# arduino-pro-micro.net
KiCad netlist of a schematic drawn in EAGLE
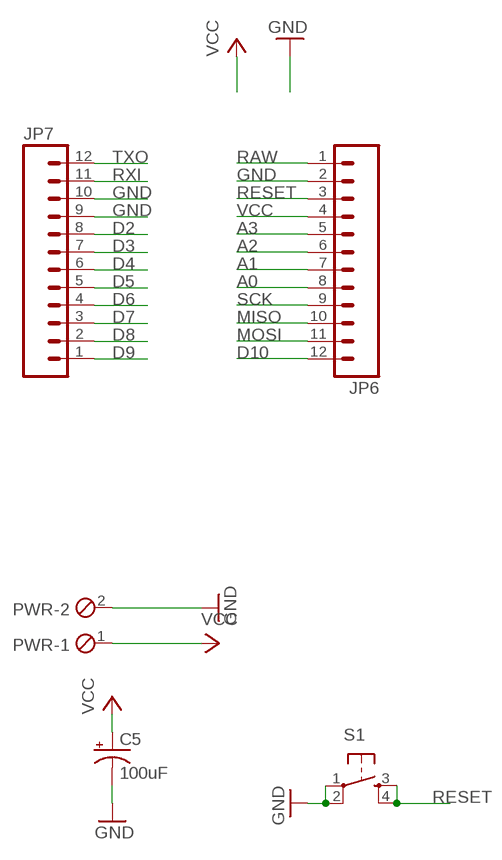
[diagram p0: schematic, sheet 1]

(export (version "E")
  (design (tool "Eeschema 10.0.6"))
  (components
    (comp (ref "C5")
      (value "100uF")
      (footprint "eagle-import:E3,5-8")
      (libsource (lib "eagle-import") (part "CPOL-USE3.5-8"))
    )
    (comp (ref "JP6")
      (value "M12PTH")
      (footprint "eagle-import:1X12")
      (libsource (lib "eagle-import") (part "M12PTH"))
    )
    (comp (ref "JP7")
      (value "M12PTH")
      (footprint "eagle-import:1X12")
      (libsource (lib "eagle-import") (part "M12PTH"))
    )
    (comp (ref "PWR")
      (value "MPT2")
      (footprint "eagle-import:2POL254")
      (libsource (lib "eagle-import") (part "MPT2"))
    )
    (comp (ref "S1")
      (value "TAC_SWITCHPTH")
      (footprint "eagle-import:TACTILE-PTH")
      (libsource (lib "eagle-import") (part "TAC_SWITCHPTH"))
    )
  )
  (nets
    (net (code "1") (name "/A0") (class "Default")
      (node (ref "JP6") (pin "8") (pinfunction "8_8") (pintype "passive"))
    )
    (net (code "2") (name "/A1") (class "Default")
      (node (ref "JP6") (pin "7") (pinfunction "7_7") (pintype "passive"))
    )
    (net (code "3") (name "/A2") (class "Default")
      (node (ref "JP6") (pin "6") (pinfunction "6_6") (pintype "passive"))
    )
    (net (code "4") (name "/A3") (class "Default")
      (node (ref "JP6") (pin "5") (pinfunction "5_5") (pintype "passive"))
    )
    (net (code "5") (name "/D2") (class "Default")
      (node (ref "JP7") (pin "8") (pinfunction "8_8") (pintype "passive"))
    )
    (net (code "6") (name "/D3") (class "Default")
      (node (ref "JP7") (pin "7") (pinfunction "7_7") (pintype "passive"))
    )
    (net (code "7") (name "/D4") (class "Default")
      (node (ref "JP7") (pin "6") (pinfunction "6_6") (pintype "passive"))
    )
    (net (code "8") (name "/D5") (class "Default")
      (node (ref "JP7") (pin "5") (pinfunction "5_5") (pintype "passive"))
    )
    (net (code "9") (name "/D6") (class "Default")
      (node (ref "JP7") (pin "4") (pinfunction "4_4") (pintype "passive"))
    )
    (net (code "10") (name "/D7") (class "Default")
      (node (ref "JP7") (pin "3") (pinfunction "3_3") (pintype "passive"))
    )
    (net (code "11") (name "/D8") (class "Default")
      (node (ref "JP7") (pin "2") (pinfunction "2_2") (pintype "passive"))
    )
    (net (code "12") (name "/D9") (class "Default")
      (node (ref "JP7") (pin "1") (pinfunction "1_1") (pintype "passive"))
    )
    (net (code "13") (name "/D10") (class "Default")
      (node (ref "JP6") (pin "12") (pinfunction "12_12") (pintype "passive"))
    )
    (net (code "14") (name "/MISO") (class "Default")
      (node (ref "JP6") (pin "10") (pinfunction "10_10") (pintype "passive"))
    )
    (net (code "15") (name "/MOSI") (class "Default")
      (node (ref "JP6") (pin "11") (pinfunction "11_11") (pintype "passive"))
    )
    (net (code "16") (name "/RAW") (class "Default")
      (node (ref "JP6") (pin "1") (pinfunction "1_1") (pintype "passive"))
    )
    (net (code "17") (name "/RESET") (class "Default")
      (node (ref "JP6") (pin "3") (pinfunction "3_3") (pintype "passive"))
      (node (ref "S1") (pin "3") (pinfunction "3_3") (pintype "passive"))
      (node (ref "S1") (pin "4") (pinfunction "4_4") (pintype "passive"))
    )
    (net (code "18") (name "/RXI") (class "Default")
      (node (ref "JP7") (pin "11") (pinfunction "11_11") (pintype "passive"))
    )
    (net (code "19") (name "/SCK") (class "Default")
      (node (ref "JP6") (pin "9") (pinfunction "9_9") (pintype "passive"))
    )
    (net (code "20") (name "/TXO") (class "Default")
      (node (ref "JP7") (pin "12") (pinfunction "12_12") (pintype "passive"))
    )
    (net (code "21") (name "GND") (class "Default")
      (node (ref "C5") (pin "-") (pinfunction "-_-") (pintype "passive"))
      (node (ref "JP6") (pin "2") (pinfunction "2_2") (pintype "passive"))
      (node (ref "JP7") (pin "10") (pinfunction "10_10") (pintype "passive"))
      (node (ref "JP7") (pin "9") (pinfunction "9_9") (pintype "passive"))
      (node (ref "PWR") (pin "2") (pinfunction "1_2") (pintype "passive"))
      (node (ref "S1") (pin "1") (pinfunction "1_1") (pintype "passive"))
      (node (ref "S1") (pin "2") (pinfunction "2_2") (pintype "passive"))
    )
    (net (code "22") (name "VCC") (class "Default")
      (node (ref "C5") (pin "+") (pinfunction "+_+") (pintype "passive"))
      (node (ref "JP6") (pin "4") (pinfunction "4_4") (pintype "passive"))
      (node (ref "PWR") (pin "1") (pinfunction "1_1") (pintype "passive"))
    )
  )
)
